# Audioaktor.net
KiCad netlist of a schematic drawn in EAGLE
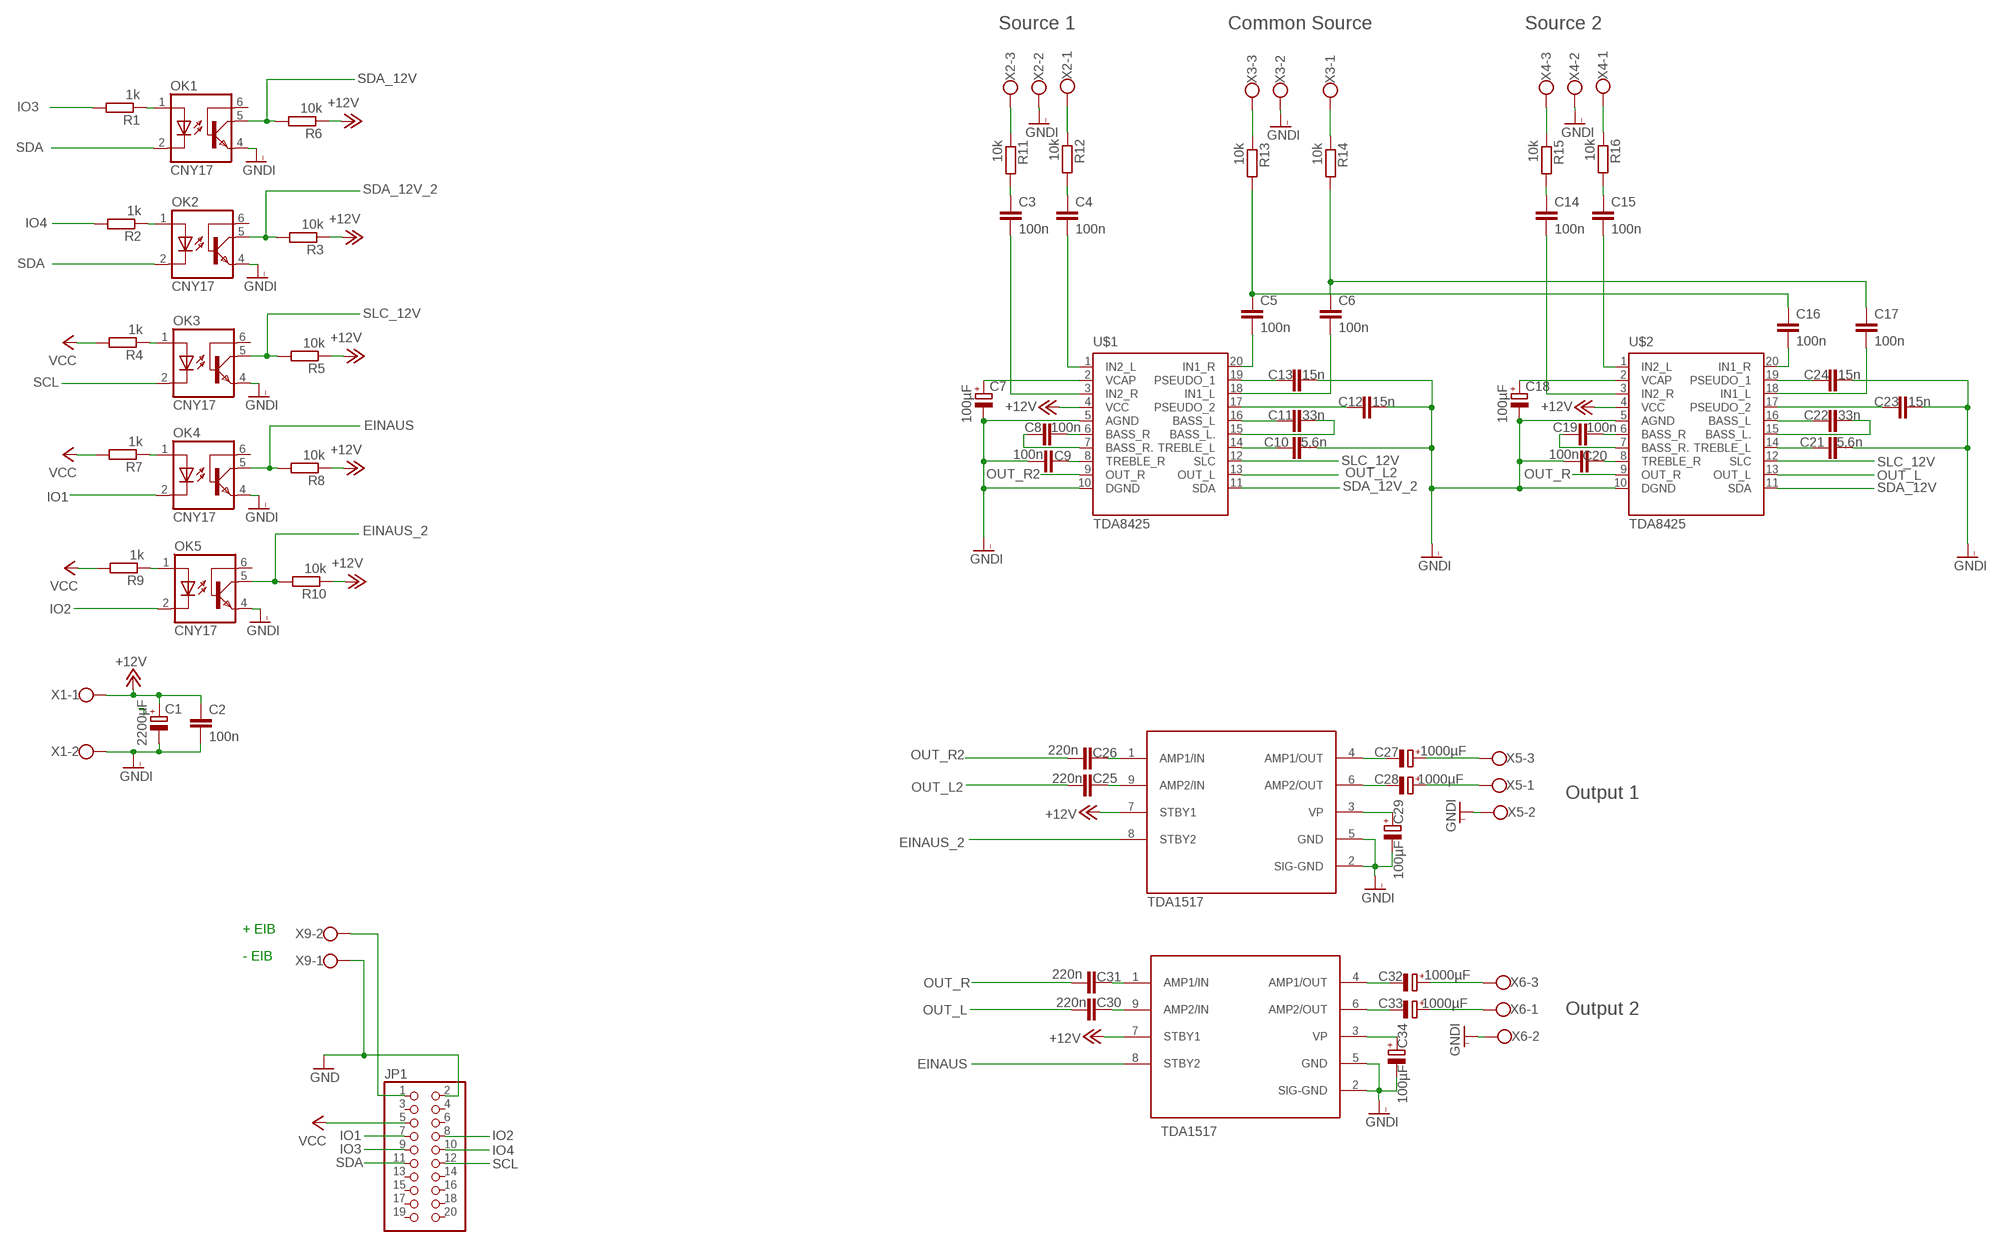
[diagram p0: schematic, sheet 1]

(export (version "E")
  (design (tool "Eeschema 10.0.6"))
  (components
    (comp (ref "C1")
      (value "2200µF")
      (footprint "eagle-import:E5-10,5")
      (libsource (lib "eagle-import") (part "CPOL-EUE5-10.5"))
    )
    (comp (ref "C2")
      (value "100n")
      (footprint "eagle-import:C050-030X075")
      (libsource (lib "eagle-import") (part "C-EU050-030X075"))
    )
    (comp (ref "C3")
      (value "100n")
      (footprint "eagle-import:C050-030X075")
      (libsource (lib "eagle-import") (part "C-EU050-030X075"))
    )
    (comp (ref "C4")
      (value "100n")
      (footprint "eagle-import:C050-030X075")
      (libsource (lib "eagle-import") (part "C-EU050-030X075"))
    )
    (comp (ref "C5")
      (value "100n")
      (footprint "eagle-import:C050-030X075")
      (libsource (lib "eagle-import") (part "C-EU050-030X075"))
    )
    (comp (ref "C6")
      (value "100n")
      (footprint "eagle-import:C050-030X075")
      (libsource (lib "eagle-import") (part "C-EU050-030X075"))
    )
    (comp (ref "C7")
      (value "100µF")
      (footprint "eagle-import:E5-10,5")
      (libsource (lib "eagle-import") (part "CPOL-EUE5-10.5"))
    )
    (comp (ref "C8")
      (value "100n")
      (footprint "eagle-import:C050-030X075")
      (libsource (lib "eagle-import") (part "C-EU050-030X075"))
    )
    (comp (ref "C9")
      (value "100n")
      (footprint "eagle-import:C050-030X075")
      (libsource (lib "eagle-import") (part "C-EU050-030X075"))
    )
    (comp (ref "C10")
      (value "5,6n")
      (footprint "eagle-import:C050-030X075")
      (libsource (lib "eagle-import") (part "C-EU050-030X075"))
    )
    (comp (ref "C11")
      (value "33n")
      (footprint "eagle-import:C050-030X075")
      (libsource (lib "eagle-import") (part "C-EU050-030X075"))
    )
    (comp (ref "C12")
      (value "15n")
      (footprint "eagle-import:C050-030X075")
      (libsource (lib "eagle-import") (part "C-EU050-030X075"))
    )
    (comp (ref "C13")
      (value "15n")
      (footprint "eagle-import:C050-030X075")
      (libsource (lib "eagle-import") (part "C-EU050-030X075"))
    )
    (comp (ref "C14")
      (value "100n")
      (footprint "eagle-import:C050-030X075")
      (libsource (lib "eagle-import") (part "C-EU050-030X075"))
    )
    (comp (ref "C15")
      (value "100n")
      (footprint "eagle-import:C050-030X075")
      (libsource (lib "eagle-import") (part "C-EU050-030X075"))
    )
    (comp (ref "C16")
      (value "100n")
      (footprint "eagle-import:C050-030X075")
      (libsource (lib "eagle-import") (part "C-EU050-030X075"))
    )
    (comp (ref "C17")
      (value "100n")
      (footprint "eagle-import:C050-030X075")
      (libsource (lib "eagle-import") (part "C-EU050-030X075"))
    )
    (comp (ref "C18")
      (value "100µF")
      (footprint "eagle-import:E5-10,5")
      (libsource (lib "eagle-import") (part "CPOL-EUE5-10.5"))
    )
    (comp (ref "C19")
      (value "100n")
      (footprint "eagle-import:C050-030X075")
      (libsource (lib "eagle-import") (part "C-EU050-030X075"))
    )
    (comp (ref "C20")
      (value "100n")
      (footprint "eagle-import:C050-030X075")
      (libsource (lib "eagle-import") (part "C-EU050-030X075"))
    )
    (comp (ref "C21")
      (value "5,6n")
      (footprint "eagle-import:C050-030X075")
      (libsource (lib "eagle-import") (part "C-EU050-030X075"))
    )
    (comp (ref "C22")
      (value "33n")
      (footprint "eagle-import:C050-030X075")
      (libsource (lib "eagle-import") (part "C-EU050-030X075"))
    )
    (comp (ref "C23")
      (value "15n")
      (footprint "eagle-import:C050-030X075")
      (libsource (lib "eagle-import") (part "C-EU050-030X075"))
    )
    (comp (ref "C24")
      (value "15n")
      (footprint "eagle-import:C050-030X075")
      (libsource (lib "eagle-import") (part "C-EU050-030X075"))
    )
    (comp (ref "C25")
      (value "220n")
      (footprint "eagle-import:C050-030X075")
      (libsource (lib "eagle-import") (part "C-EU050-030X075"))
    )
    (comp (ref "C26")
      (value "220n")
      (footprint "eagle-import:C050-030X075")
      (libsource (lib "eagle-import") (part "C-EU050-030X075"))
    )
    (comp (ref "C27")
      (value "1000µF")
      (footprint "eagle-import:E5-10,5")
      (libsource (lib "eagle-import") (part "CPOL-EUE5-10.5"))
    )
    (comp (ref "C28")
      (value "1000µF")
      (footprint "eagle-import:E5-10,5")
      (libsource (lib "eagle-import") (part "CPOL-EUE5-10.5"))
    )
    (comp (ref "C29")
      (value "100µF")
      (footprint "eagle-import:E5-10,5")
      (libsource (lib "eagle-import") (part "CPOL-EUE5-10.5"))
    )
    (comp (ref "C30")
      (value "220n")
      (footprint "eagle-import:C050-030X075")
      (libsource (lib "eagle-import") (part "C-EU050-030X075"))
    )
    (comp (ref "C31")
      (value "220n")
      (footprint "eagle-import:C050-030X075")
      (libsource (lib "eagle-import") (part "C-EU050-030X075"))
    )
    (comp (ref "C32")
      (value "1000µF")
      (footprint "eagle-import:E5-10,5")
      (libsource (lib "eagle-import") (part "CPOL-EUE5-10.5"))
    )
    (comp (ref "C33")
      (value "1000µF")
      (footprint "eagle-import:E5-10,5")
      (libsource (lib "eagle-import") (part "CPOL-EUE5-10.5"))
    )
    (comp (ref "C34")
      (value "100µF")
      (footprint "eagle-import:E5-10,5")
      (libsource (lib "eagle-import") (part "CPOL-EUE5-10.5"))
    )
    (comp (ref "JP1")
      (value "PINHD-2X10")
      (footprint "eagle-import:2X10")
      (libsource (lib "eagle-import") (part "PINHD-2X10"))
    )
    (comp (ref "OK1")
      (value "CNY17")
      (footprint "eagle-import:DIL06")
      (libsource (lib "eagle-import") (part "CNY17"))
    )
    (comp (ref "OK2")
      (value "CNY17")
      (footprint "eagle-import:DIL06")
      (libsource (lib "eagle-import") (part "CNY17"))
    )
    (comp (ref "OK3")
      (value "CNY17")
      (footprint "eagle-import:DIL06")
      (libsource (lib "eagle-import") (part "CNY17"))
    )
    (comp (ref "OK4")
      (value "CNY17")
      (footprint "eagle-import:DIL06")
      (libsource (lib "eagle-import") (part "CNY17"))
    )
    (comp (ref "OK5")
      (value "CNY17")
      (footprint "eagle-import:DIL06")
      (libsource (lib "eagle-import") (part "CNY17"))
    )
    (comp (ref "R1")
      (value "1k")
      (footprint "eagle-import:0204_7")
      (libsource (lib "eagle-import") (part "R-EU_0204/7"))
    )
    (comp (ref "R2")
      (value "1k")
      (footprint "eagle-import:0204_7")
      (libsource (lib "eagle-import") (part "R-EU_0204/7"))
    )
    (comp (ref "R3")
      (value "10k")
      (footprint "eagle-import:0204_7")
      (libsource (lib "eagle-import") (part "R-EU_0204/7"))
    )
    (comp (ref "R4")
      (value "1k")
      (footprint "eagle-import:0204_7")
      (libsource (lib "eagle-import") (part "R-EU_0204/7"))
    )
    (comp (ref "R5")
      (value "10k")
      (footprint "eagle-import:0204_7")
      (libsource (lib "eagle-import") (part "R-EU_0204/7"))
    )
    (comp (ref "R6")
      (value "10k")
      (footprint "eagle-import:0204_7")
      (libsource (lib "eagle-import") (part "R-EU_0204/7"))
    )
    (comp (ref "R7")
      (value "1k")
      (footprint "eagle-import:0204_7")
      (libsource (lib "eagle-import") (part "R-EU_0204/7"))
    )
    (comp (ref "R8")
      (value "10k")
      (footprint "eagle-import:0204_7")
      (libsource (lib "eagle-import") (part "R-EU_0204/7"))
    )
    (comp (ref "R9")
      (value "1k")
      (footprint "eagle-import:0204_7")
      (libsource (lib "eagle-import") (part "R-EU_0204/7"))
    )
    (comp (ref "R10")
      (value "10k")
      (footprint "eagle-import:0204_7")
      (libsource (lib "eagle-import") (part "R-EU_0204/7"))
    )
    (comp (ref "R11")
      (value "10k")
      (footprint "eagle-import:0204_7")
      (libsource (lib "eagle-import") (part "R-EU_0204/7"))
    )
    (comp (ref "R12")
      (value "10k")
      (footprint "eagle-import:0204_7")
      (libsource (lib "eagle-import") (part "R-EU_0204/7"))
    )
    (comp (ref "R13")
      (value "10k")
      (footprint "eagle-import:0204_7")
      (libsource (lib "eagle-import") (part "R-EU_0204/7"))
    )
    (comp (ref "R14")
      (value "10k")
      (footprint "eagle-import:0204_7")
      (libsource (lib "eagle-import") (part "R-EU_0204/7"))
    )
    (comp (ref "R15")
      (value "10k")
      (footprint "eagle-import:0204_7")
      (libsource (lib "eagle-import") (part "R-EU_0204/7"))
    )
    (comp (ref "R16")
      (value "10k")
      (footprint "eagle-import:0204_7")
      (libsource (lib "eagle-import") (part "R-EU_0204/7"))
    )
    (comp (ref "TDA1517")
      (value "TDA1517")
      (footprint "eagle-import:TDA1517")
      (libsource (lib "eagle-import") (part "TDA1517"))
    )
    (comp (ref "U$1")
      (value "TDA8425")
      (footprint "eagle-import:DIL20")
      (libsource (lib "eagle-import") (part "TDA8425"))
    )
    (comp (ref "U$2")
      (value "TDA8425")
      (footprint "eagle-import:DIL20")
      (libsource (lib "eagle-import") (part "TDA8425"))
    )
    (comp (ref "U$3")
      (value "TDA1517")
      (footprint "eagle-import:TDA1517")
      (libsource (lib "eagle-import") (part "TDA1517"))
    )
    (comp (ref "X1")
      (value "W237-102")
      (footprint "eagle-import:W237-102")
      (libsource (lib "eagle-import") (part "W237-102"))
    )
    (comp (ref "X2")
      (value "W237-103")
      (footprint "eagle-import:W237-103")
      (libsource (lib "eagle-import") (part "W237-103"))
    )
    (comp (ref "X3")
      (value "W237-103")
      (footprint "eagle-import:W237-103")
      (libsource (lib "eagle-import") (part "W237-103"))
    )
    (comp (ref "X4")
      (value "W237-103")
      (footprint "eagle-import:W237-103")
      (libsource (lib "eagle-import") (part "W237-103"))
    )
    (comp (ref "X5")
      (value "W237-103")
      (footprint "eagle-import:W237-103")
      (libsource (lib "eagle-import") (part "W237-103"))
    )
    (comp (ref "X6")
      (value "W237-103")
      (footprint "eagle-import:W237-103")
      (libsource (lib "eagle-import") (part "W237-103"))
    )
    (comp (ref "X9")
      (value "W237-102")
      (footprint "eagle-import:W237-102")
      (libsource (lib "eagle-import") (part "W237-102"))
    )
  )
  (nets
    (net (code "1") (name "+12V") (class "Default")
      (node (ref "C1") (pin "+") (pinfunction "+_+") (pintype "passive"))
      (node (ref "C2") (pin "1") (pinfunction "1_1") (pintype "passive"))
      (node (ref "R10") (pin "1") (pinfunction "1_1") (pintype "passive"))
      (node (ref "R3") (pin "1") (pinfunction "1_1") (pintype "passive"))
      (node (ref "R5") (pin "1") (pinfunction "1_1") (pintype "passive"))
      (node (ref "R6") (pin "1") (pinfunction "1_1") (pintype "passive"))
      (node (ref "R8") (pin "1") (pinfunction "1_1") (pintype "passive"))
      (node (ref "TDA1517") (pin "7") (pinfunction "STBY1_7") (pintype "bidirectional"))
      (node (ref "U$1") (pin "4") (pinfunction "VCC_4") (pintype "input"))
      (node (ref "U$2") (pin "4") (pinfunction "VCC_4") (pintype "input"))
      (node (ref "U$3") (pin "7") (pinfunction "STBY1_7") (pintype "bidirectional"))
      (node (ref "X1") (pin "1") (pinfunction "KL_1") (pintype "passive"))
    )
    (net (code "2") (name "/EINAUS") (class "Default")
      (node (ref "OK4") (pin "5") (pinfunction "COL_5") (pintype "passive"))
      (node (ref "R8") (pin "2") (pinfunction "2_2") (pintype "passive"))
      (node (ref "TDA1517") (pin "8") (pinfunction "STBY2_8") (pintype "bidirectional"))
    )
    (net (code "3") (name "/EINAUS_2") (class "Default")
      (node (ref "OK5") (pin "5") (pinfunction "COL_5") (pintype "passive"))
      (node (ref "R10") (pin "2") (pinfunction "2_2") (pintype "passive"))
      (node (ref "U$3") (pin "8") (pinfunction "STBY2_8") (pintype "bidirectional"))
    )
    (net (code "4") (name "/IO1") (class "Default")
      (node (ref "JP1") (pin "7") (pinfunction "7_7") (pintype "passive"))
      (node (ref "OK4") (pin "2") (pinfunction "C_2") (pintype "passive"))
    )
    (net (code "5") (name "/IO2") (class "Default")
      (node (ref "JP1") (pin "8") (pinfunction "8_8") (pintype "passive"))
      (node (ref "OK5") (pin "2") (pinfunction "C_2") (pintype "passive"))
    )
    (net (code "6") (name "/IO3") (class "Default")
      (node (ref "JP1") (pin "9") (pinfunction "9_9") (pintype "passive"))
      (node (ref "R1") (pin "2") (pinfunction "2_2") (pintype "passive"))
    )
    (net (code "7") (name "/IO4") (class "Default")
      (node (ref "JP1") (pin "10") (pinfunction "10_10") (pintype "passive"))
      (node (ref "R2") (pin "2") (pinfunction "2_2") (pintype "passive"))
    )
    (net (code "8") (name "/OUT_L") (class "Default")
      (node (ref "C30") (pin "1") (pinfunction "1_1") (pintype "passive"))
      (node (ref "U$2") (pin "13") (pinfunction "OUT_L_13") (pintype "input"))
    )
    (net (code "9") (name "/OUT_L2") (class "Default")
      (node (ref "C25") (pin "1") (pinfunction "1_1") (pintype "passive"))
      (node (ref "U$1") (pin "13") (pinfunction "OUT_L_13") (pintype "input"))
    )
    (net (code "10") (name "/OUT_R") (class "Default")
      (node (ref "C31") (pin "1") (pinfunction "1_1") (pintype "passive"))
      (node (ref "U$2") (pin "9") (pinfunction "OUT_R_9") (pintype "input"))
    )
    (net (code "11") (name "/OUT_R2") (class "Default")
      (node (ref "C26") (pin "1") (pinfunction "1_1") (pintype "passive"))
      (node (ref "U$1") (pin "9") (pinfunction "OUT_R_9") (pintype "input"))
    )
    (net (code "12") (name "/SCL") (class "Default")
      (node (ref "JP1") (pin "12") (pinfunction "12_12") (pintype "passive"))
      (node (ref "OK3") (pin "2") (pinfunction "C_2") (pintype "passive"))
    )
    (net (code "13") (name "/SDA") (class "Default")
      (node (ref "JP1") (pin "11") (pinfunction "11_11") (pintype "passive"))
      (node (ref "OK1") (pin "2") (pinfunction "C_2") (pintype "passive"))
      (node (ref "OK2") (pin "2") (pinfunction "C_2") (pintype "passive"))
    )
    (net (code "14") (name "/SDA_12V") (class "Default")
      (node (ref "OK1") (pin "5") (pinfunction "COL_5") (pintype "passive"))
      (node (ref "R6") (pin "2") (pinfunction "2_2") (pintype "passive"))
      (node (ref "U$2") (pin "11") (pinfunction "SDA_11") (pintype "input"))
    )
    (net (code "15") (name "/SDA_12V_2") (class "Default")
      (node (ref "OK2") (pin "5") (pinfunction "COL_5") (pintype "passive"))
      (node (ref "R3") (pin "2") (pinfunction "2_2") (pintype "passive"))
      (node (ref "U$1") (pin "11") (pinfunction "SDA_11") (pintype "input"))
    )
    (net (code "16") (name "/SLC_12V") (class "Default")
      (node (ref "OK3") (pin "5") (pinfunction "COL_5") (pintype "passive"))
      (node (ref "R5") (pin "2") (pinfunction "2_2") (pintype "passive"))
      (node (ref "U$1") (pin "12") (pinfunction "SLC_12") (pintype "passive"))
      (node (ref "U$2") (pin "12") (pinfunction "SLC_12") (pintype "passive"))
    )
    (net (code "17") (name "GND") (class "Default")
      (node (ref "JP1") (pin "2") (pinfunction "2_2") (pintype "passive"))
      (node (ref "X9") (pin "1") (pinfunction "KL_1") (pintype "passive"))
    )
    (net (code "18") (name "GNDI") (class "Default")
      (node (ref "C1") (pin "-") (pinfunction "-_-") (pintype "passive"))
      (node (ref "C10") (pin "2") (pinfunction "2_2") (pintype "passive"))
      (node (ref "C12") (pin "2") (pinfunction "2_2") (pintype "passive"))
      (node (ref "C13") (pin "2") (pinfunction "2_2") (pintype "passive"))
      (node (ref "C18") (pin "-") (pinfunction "-_-") (pintype "passive"))
      (node (ref "C2") (pin "2") (pinfunction "2_2") (pintype "passive"))
      (node (ref "C20") (pin "1") (pinfunction "1_1") (pintype "passive"))
      (node (ref "C21") (pin "2") (pinfunction "2_2") (pintype "passive"))
      (node (ref "C23") (pin "2") (pinfunction "2_2") (pintype "passive"))
      (node (ref "C24") (pin "2") (pinfunction "2_2") (pintype "passive"))
      (node (ref "C29") (pin "-") (pinfunction "-_-") (pintype "passive"))
      (node (ref "C34") (pin "-") (pinfunction "-_-") (pintype "passive"))
      (node (ref "C7") (pin "-") (pinfunction "-_-") (pintype "passive"))
      (node (ref "C9") (pin "1") (pinfunction "1_1") (pintype "passive"))
      (node (ref "OK1") (pin "4") (pinfunction "EMI_4") (pintype "passive"))
      (node (ref "OK2") (pin "4") (pinfunction "EMI_4") (pintype "passive"))
      (node (ref "OK3") (pin "4") (pinfunction "EMI_4") (pintype "passive"))
      (node (ref "OK4") (pin "4") (pinfunction "EMI_4") (pintype "passive"))
      (node (ref "OK5") (pin "4") (pinfunction "EMI_4") (pintype "passive"))
      (node (ref "TDA1517") (pin "2") (pinfunction "SIG-GND_2") (pintype "bidirectional"))
      (node (ref "TDA1517") (pin "5") (pinfunction "GND_5") (pintype "bidirectional"))
      (node (ref "U$1") (pin "10") (pinfunction "DGND_10") (pintype "input"))
      (node (ref "U$1") (pin "5") (pinfunction "AGND_5") (pintype "input"))
      (node (ref "U$2") (pin "10") (pinfunction "DGND_10") (pintype "input"))
      (node (ref "U$2") (pin "5") (pinfunction "AGND_5") (pintype "input"))
      (node (ref "U$3") (pin "2") (pinfunction "SIG-GND_2") (pintype "bidirectional"))
      (node (ref "U$3") (pin "5") (pinfunction "GND_5") (pintype "bidirectional"))
      (node (ref "X1") (pin "2") (pinfunction "KL_2") (pintype "passive"))
      (node (ref "X2") (pin "2") (pinfunction "KL_2") (pintype "passive"))
      (node (ref "X3") (pin "2") (pinfunction "KL_2") (pintype "passive"))
      (node (ref "X4") (pin "2") (pinfunction "KL_2") (pintype "passive"))
      (node (ref "X5") (pin "2") (pinfunction "KL_2") (pintype "passive"))
      (node (ref "X6") (pin "2") (pinfunction "KL_2") (pintype "passive"))
    )
    (net (code "19") (name "Net-(C3-Pad1)") (class "Default")
      (node (ref "C3") (pin "1") (pinfunction "1_1") (pintype "passive"))
      (node (ref "R11") (pin "2") (pinfunction "2_2") (pintype "passive"))
    )
    (net (code "20") (name "Net-(C4-Pad1)") (class "Default")
      (node (ref "C4") (pin "1") (pinfunction "1_1") (pintype "passive"))
      (node (ref "R12") (pin "2") (pinfunction "2_2") (pintype "passive"))
    )
    (net (code "21") (name "Net-(C14-Pad1)") (class "Default")
      (node (ref "C14") (pin "1") (pinfunction "1_1") (pintype "passive"))
      (node (ref "R15") (pin "2") (pinfunction "2_2") (pintype "passive"))
    )
    (net (code "22") (name "Net-(C15-Pad1)") (class "Default")
      (node (ref "C15") (pin "1") (pinfunction "1_1") (pintype "passive"))
      (node (ref "R16") (pin "2") (pinfunction "2_2") (pintype "passive"))
    )
    (net (code "23") (name "Net-(C16-Pad1)") (class "Default")
      (node (ref "C16") (pin "1") (pinfunction "1_1") (pintype "passive"))
      (node (ref "C5") (pin "1") (pinfunction "1_1") (pintype "passive"))
      (node (ref "R13") (pin "2") (pinfunction "2_2") (pintype "passive"))
    )
    (net (code "24") (name "Net-(C17-Pad1)") (class "Default")
      (node (ref "C17") (pin "1") (pinfunction "1_1") (pintype "passive"))
      (node (ref "C6") (pin "1") (pinfunction "1_1") (pintype "passive"))
      (node (ref "R14") (pin "2") (pinfunction "2_2") (pintype "passive"))
    )
    (net (code "25") (name "Net-(OK1-A)") (class "Default")
      (node (ref "OK1") (pin "1") (pinfunction "A_1") (pintype "passive"))
      (node (ref "R1") (pin "1") (pinfunction "1_1") (pintype "passive"))
    )
    (net (code "26") (name "Net-(OK2-A)") (class "Default")
      (node (ref "OK2") (pin "1") (pinfunction "A_1") (pintype "passive"))
      (node (ref "R2") (pin "1") (pinfunction "1_1") (pintype "passive"))
    )
    (net (code "27") (name "Net-(OK3-A)") (class "Default")
      (node (ref "OK3") (pin "1") (pinfunction "A_1") (pintype "passive"))
      (node (ref "R4") (pin "1") (pinfunction "1_1") (pintype "passive"))
    )
    (net (code "28") (name "Net-(OK4-A)") (class "Default")
      (node (ref "OK4") (pin "1") (pinfunction "A_1") (pintype "passive"))
      (node (ref "R7") (pin "1") (pinfunction "1_1") (pintype "passive"))
    )
    (net (code "29") (name "Net-(OK5-A)") (class "Default")
      (node (ref "OK5") (pin "1") (pinfunction "A_1") (pintype "passive"))
      (node (ref "R9") (pin "1") (pinfunction "1_1") (pintype "passive"))
    )
    (net (code "30") (name "Net-(TDA1517-AMP1{slash}IN)") (class "Default")
      (node (ref "C31") (pin "2") (pinfunction "2_2") (pintype "passive"))
      (node (ref "TDA1517") (pin "1") (pinfunction "AMP1/IN_1") (pintype "bidirectional"))
    )
    (net (code "31") (name "Net-(TDA1517-AMP1{slash}OUT)") (class "Default")
      (node (ref "C32") (pin "-") (pinfunction "-_-") (pintype "passive"))
      (node (ref "TDA1517") (pin "4") (pinfunction "AMP1/OUT_4") (pintype "bidirectional"))
    )
    (net (code "32") (name "Net-(TDA1517-AMP2{slash}IN)") (class "Default")
      (node (ref "C30") (pin "2") (pinfunction "2_2") (pintype "passive"))
      (node (ref "TDA1517") (pin "9") (pinfunction "AMP2/IN_9") (pintype "bidirectional"))
    )
    (net (code "33") (name "Net-(TDA1517-AMP2{slash}OUT)") (class "Default")
      (node (ref "C33") (pin "-") (pinfunction "-_-") (pintype "passive"))
      (node (ref "TDA1517") (pin "6") (pinfunction "AMP2/OUT_6") (pintype "bidirectional"))
    )
    (net (code "34") (name "Net-(TDA1517-VP)") (class "Default")
      (node (ref "C34") (pin "+") (pinfunction "+_+") (pintype "passive"))
      (node (ref "TDA1517") (pin "3") (pinfunction "VP_3") (pintype "bidirectional"))
    )
    (net (code "35") (name "Net-(U$1-BASS_L)") (class "Default")
      (node (ref "C11") (pin "1") (pinfunction "1_1") (pintype "passive"))
      (node (ref "U$1") (pin "16") (pinfunction "BASS_L_16") (pintype "output"))
    )
    (net (code "36") (name "Net-(U$1-BASS_L.)") (class "Default")
      (node (ref "C11") (pin "2") (pinfunction "2_2") (pintype "passive"))
      (node (ref "U$1") (pin "15") (pinfunction "BASS_L._15") (pintype "output"))
    )
    (net (code "37") (name "Net-(U$1-BASS_R)") (class "Default")
      (node (ref "C8") (pin "2") (pinfunction "2_2") (pintype "passive"))
      (node (ref "U$1") (pin "6") (pinfunction "BASS_R_6") (pintype "input"))
    )
    (net (code "38") (name "Net-(U$1-BASS_R.)") (class "Default")
      (node (ref "C8") (pin "1") (pinfunction "1_1") (pintype "passive"))
      (node (ref "U$1") (pin "7") (pinfunction "BASS_R._7") (pintype "input"))
    )
    (net (code "39") (name "Net-(U$1-IN1_L)") (class "Default")
      (node (ref "C6") (pin "2") (pinfunction "2_2") (pintype "passive"))
      (node (ref "U$1") (pin "18") (pinfunction "IN1_L_18") (pintype "output"))
    )
    (net (code "40") (name "Net-(U$1-IN1_R)") (class "Default")
      (node (ref "C5") (pin "2") (pinfunction "2_2") (pintype "passive"))
      (node (ref "U$1") (pin "20") (pinfunction "IN1_R_20") (pintype "passive"))
    )
    (net (code "41") (name "Net-(U$1-IN2_L)") (class "Default")
      (node (ref "C4") (pin "2") (pinfunction "2_2") (pintype "passive"))
      (node (ref "U$1") (pin "1") (pinfunction "IN2_L_1") (pintype "passive"))
    )
    (net (code "42") (name "Net-(U$1-IN2_R)") (class "Default")
      (node (ref "C3") (pin "2") (pinfunction "2_2") (pintype "passive"))
      (node (ref "U$1") (pin "3") (pinfunction "IN2_R_3") (pintype "passive"))
    )
    (net (code "43") (name "Net-(U$1-PSEUDO_1)") (class "Default")
      (node (ref "C13") (pin "1") (pinfunction "1_1") (pintype "passive"))
      (node (ref "U$1") (pin "19") (pinfunction "PSEUDO_1_19") (pintype "passive"))
    )
    (net (code "44") (name "Net-(U$1-PSEUDO_2)") (class "Default")
      (node (ref "C12") (pin "1") (pinfunction "1_1") (pintype "passive"))
      (node (ref "U$1") (pin "17") (pinfunction "PSEUDO_2_17") (pintype "passive"))
    )
    (net (code "45") (name "Net-(U$1-TREBLE_L)") (class "Default")
      (node (ref "C10") (pin "1") (pinfunction "1_1") (pintype "passive"))
      (node (ref "U$1") (pin "14") (pinfunction "TREBLE_L_14") (pintype "output"))
    )
    (net (code "46") (name "Net-(U$1-TREBLE_R)") (class "Default")
      (node (ref "C9") (pin "2") (pinfunction "2_2") (pintype "passive"))
      (node (ref "U$1") (pin "8") (pinfunction "TREBLE_R_8") (pintype "input"))
    )
    (net (code "47") (name "Net-(U$1-VCAP)") (class "Default")
      (node (ref "C7") (pin "+") (pinfunction "+_+") (pintype "passive"))
      (node (ref "U$1") (pin "2") (pinfunction "VCAP_2") (pintype "passive"))
    )
    (net (code "48") (name "Net-(U$2-BASS_L)") (class "Default")
      (node (ref "C22") (pin "1") (pinfunction "1_1") (pintype "passive"))
      (node (ref "U$2") (pin "16") (pinfunction "BASS_L_16") (pintype "output"))
    )
    (net (code "49") (name "Net-(U$2-BASS_L.)") (class "Default")
      (node (ref "C22") (pin "2") (pinfunction "2_2") (pintype "passive"))
      (node (ref "U$2") (pin "15") (pinfunction "BASS_L._15") (pintype "output"))
    )
    (net (code "50") (name "Net-(U$2-BASS_R)") (class "Default")
      (node (ref "C19") (pin "2") (pinfunction "2_2") (pintype "passive"))
      (node (ref "U$2") (pin "6") (pinfunction "BASS_R_6") (pintype "input"))
    )
    (net (code "51") (name "Net-(U$2-BASS_R.)") (class "Default")
      (node (ref "C19") (pin "1") (pinfunction "1_1") (pintype "passive"))
      (node (ref "U$2") (pin "7") (pinfunction "BASS_R._7") (pintype "input"))
    )
    (net (code "52") (name "Net-(U$2-IN1_L)") (class "Default")
      (node (ref "C17") (pin "2") (pinfunction "2_2") (pintype "passive"))
      (node (ref "U$2") (pin "18") (pinfunction "IN1_L_18") (pintype "output"))
    )
    (net (code "53") (name "Net-(U$2-IN1_R)") (class "Default")
      (node (ref "C16") (pin "2") (pinfunction "2_2") (pintype "passive"))
      (node (ref "U$2") (pin "20") (pinfunction "IN1_R_20") (pintype "passive"))
    )
    (net (code "54") (name "Net-(U$2-IN2_L)") (class "Default")
      (node (ref "C15") (pin "2") (pinfunction "2_2") (pintype "passive"))
      (node (ref "U$2") (pin "1") (pinfunction "IN2_L_1") (pintype "passive"))
    )
    (net (code "55") (name "Net-(U$2-IN2_R)") (class "Default")
      (node (ref "C14") (pin "2") (pinfunction "2_2") (pintype "passive"))
      (node (ref "U$2") (pin "3") (pinfunction "IN2_R_3") (pintype "passive"))
    )
    (net (code "56") (name "Net-(U$2-PSEUDO_1)") (class "Default")
      (node (ref "C24") (pin "1") (pinfunction "1_1") (pintype "passive"))
      (node (ref "U$2") (pin "19") (pinfunction "PSEUDO_1_19") (pintype "passive"))
    )
    (net (code "57") (name "Net-(U$2-PSEUDO_2)") (class "Default")
      (node (ref "C23") (pin "1") (pinfunction "1_1") (pintype "passive"))
      (node (ref "U$2") (pin "17") (pinfunction "PSEUDO_2_17") (pintype "passive"))
    )
    (net (code "58") (name "Net-(U$2-TREBLE_L)") (class "Default")
      (node (ref "C21") (pin "1") (pinfunction "1_1") (pintype "passive"))
      (node (ref "U$2") (pin "14") (pinfunction "TREBLE_L_14") (pintype "output"))
    )
    (net (code "59") (name "Net-(U$2-TREBLE_R)") (class "Default")
      (node (ref "C20") (pin "2") (pinfunction "2_2") (pintype "passive"))
      (node (ref "U$2") (pin "8") (pinfunction "TREBLE_R_8") (pintype "input"))
    )
    (net (code "60") (name "Net-(U$2-VCAP)") (class "Default")
      (node (ref "C18") (pin "+") (pinfunction "+_+") (pintype "passive"))
      (node (ref "U$2") (pin "2") (pinfunction "VCAP_2") (pintype "passive"))
    )
    (net (code "61") (name "Net-(U$3-AMP1{slash}IN)") (class "Default")
      (node (ref "C26") (pin "2") (pinfunction "2_2") (pintype "passive"))
      (node (ref "U$3") (pin "1") (pinfunction "AMP1/IN_1") (pintype "bidirectional"))
    )
    (net (code "62") (name "Net-(U$3-AMP1{slash}OUT)") (class "Default")
      (node (ref "C27") (pin "-") (pinfunction "-_-") (pintype "passive"))
      (node (ref "U$3") (pin "4") (pinfunction "AMP1/OUT_4") (pintype "bidirectional"))
    )
    (net (code "63") (name "Net-(U$3-AMP2{slash}IN)") (class "Default")
      (node (ref "C25") (pin "2") (pinfunction "2_2") (pintype "passive"))
      (node (ref "U$3") (pin "9") (pinfunction "AMP2/IN_9") (pintype "bidirectional"))
    )
    (net (code "64") (name "Net-(U$3-AMP2{slash}OUT)") (class "Default")
      (node (ref "C28") (pin "-") (pinfunction "-_-") (pintype "passive"))
      (node (ref "U$3") (pin "6") (pinfunction "AMP2/OUT_6") (pintype "bidirectional"))
    )
    (net (code "65") (name "Net-(U$3-VP)") (class "Default")
      (node (ref "C29") (pin "+") (pinfunction "+_+") (pintype "passive"))
      (node (ref "U$3") (pin "3") (pinfunction "VP_3") (pintype "bidirectional"))
    )
    (net (code "66") (name "Net-(X2A-KL)") (class "Default")
      (node (ref "R12") (pin "1") (pinfunction "1_1") (pintype "passive"))
      (node (ref "X2") (pin "1") (pinfunction "KL_1") (pintype "passive"))
    )
    (net (code "67") (name "Net-(X2C-KL)") (class "Default")
      (node (ref "R11") (pin "1") (pinfunction "1_1") (pintype "passive"))
      (node (ref "X2") (pin "3") (pinfunction "KL_3") (pintype "passive"))
    )
    (net (code "68") (name "Net-(X3A-KL)") (class "Default")
      (node (ref "R14") (pin "1") (pinfunction "1_1") (pintype "passive"))
      (node (ref "X3") (pin "1") (pinfunction "KL_1") (pintype "passive"))
    )
    (net (code "69") (name "Net-(X3C-KL)") (class "Default")
      (node (ref "R13") (pin "1") (pinfunction "1_1") (pintype "passive"))
      (node (ref "X3") (pin "3") (pinfunction "KL_3") (pintype "passive"))
    )
    (net (code "70") (name "Net-(X4A-KL)") (class "Default")
      (node (ref "R16") (pin "1") (pinfunction "1_1") (pintype "passive"))
      (node (ref "X4") (pin "1") (pinfunction "KL_1") (pintype "passive"))
    )
    (net (code "71") (name "Net-(X4C-KL)") (class "Default")
      (node (ref "R15") (pin "1") (pinfunction "1_1") (pintype "passive"))
      (node (ref "X4") (pin "3") (pinfunction "KL_3") (pintype "passive"))
    )
    (net (code "72") (name "Net-(X5A-KL)") (class "Default")
      (node (ref "C28") (pin "+") (pinfunction "+_+") (pintype "passive"))
      (node (ref "X5") (pin "1") (pinfunction "KL_1") (pintype "passive"))
    )
    (net (code "73") (name "Net-(X5C-KL)") (class "Default")
      (node (ref "C27") (pin "+") (pinfunction "+_+") (pintype "passive"))
      (node (ref "X5") (pin "3") (pinfunction "KL_3") (pintype "passive"))
    )
    (net (code "74") (name "Net-(X6A-KL)") (class "Default")
      (node (ref "C33") (pin "+") (pinfunction "+_+") (pintype "passive"))
      (node (ref "X6") (pin "1") (pinfunction "KL_1") (pintype "passive"))
    )
    (net (code "75") (name "Net-(X6C-KL)") (class "Default")
      (node (ref "C32") (pin "+") (pinfunction "+_+") (pintype "passive"))
      (node (ref "X6") (pin "3") (pinfunction "KL_3") (pintype "passive"))
    )
    (net (code "76") (name "Net-(X9B-KL)") (class "Default")
      (node (ref "JP1") (pin "1") (pinfunction "1_1") (pintype "passive"))
      (node (ref "X9") (pin "2") (pinfunction "KL_2") (pintype "passive"))
    )
    (net (code "77") (name "VCC") (class "Default")
      (node (ref "JP1") (pin "5") (pinfunction "5_5") (pintype "passive"))
      (node (ref "R4") (pin "2") (pinfunction "2_2") (pintype "passive"))
      (node (ref "R7") (pin "2") (pinfunction "2_2") (pintype "passive"))
      (node (ref "R9") (pin "2") (pinfunction "2_2") (pintype "passive"))
    )
    (net (code "78") (name "unconnected-(JP1-Pad3)") (class "Default")
      (node (ref "JP1") (pin "3") (pinfunction "3_3") (pintype "passive"))
    )
    (net (code "79") (name "unconnected-(JP1-Pad4)") (class "Default")
      (node (ref "JP1") (pin "4") (pinfunction "4_4") (pintype "passive"))
    )
    (net (code "80") (name "unconnected-(JP1-Pad6)") (class "Default")
      (node (ref "JP1") (pin "6") (pinfunction "6_6") (pintype "passive"))
    )
    (net (code "81") (name "unconnected-(JP1-Pad13)") (class "Default")
      (node (ref "JP1") (pin "13") (pinfunction "13_13") (pintype "passive"))
    )
    (net (code "82") (name "unconnected-(JP1-Pad14)") (class "Default")
      (node (ref "JP1") (pin "14") (pinfunction "14_14") (pintype "passive"))
    )
    (net (code "83") (name "unconnected-(JP1-Pad15)") (class "Default")
      (node (ref "JP1") (pin "15") (pinfunction "15_15") (pintype "passive"))
    )
    (net (code "84") (name "unconnected-(JP1-Pad16)") (class "Default")
      (node (ref "JP1") (pin "16") (pinfunction "16_16") (pintype "passive"))
    )
    (net (code "85") (name "unconnected-(JP1-Pad17)") (class "Default")
      (node (ref "JP1") (pin "17") (pinfunction "17_17") (pintype "passive"))
    )
    (net (code "86") (name "unconnected-(JP1-Pad18)") (class "Default")
      (node (ref "JP1") (pin "18") (pinfunction "18_18") (pintype "passive"))
    )
    (net (code "87") (name "unconnected-(JP1-Pad19)") (class "Default")
      (node (ref "JP1") (pin "19") (pinfunction "19_19") (pintype "passive"))
    )
    (net (code "88") (name "unconnected-(JP1-Pad20)") (class "Default")
      (node (ref "JP1") (pin "20") (pinfunction "20_20") (pintype "passive"))
    )
    (net (code "89") (name "unconnected-(OK1-BAS-Pad6)") (class "Default")
      (node (ref "OK1") (pin "6") (pinfunction "BAS_6") (pintype "passive"))
    )
    (net (code "90") (name "unconnected-(OK2-BAS-Pad6)") (class "Default")
      (node (ref "OK2") (pin "6") (pinfunction "BAS_6") (pintype "passive"))
    )
    (net (code "91") (name "unconnected-(OK3-BAS-Pad6)") (class "Default")
      (node (ref "OK3") (pin "6") (pinfunction "BAS_6") (pintype "passive"))
    )
    (net (code "92") (name "unconnected-(OK4-BAS-Pad6)") (class "Default")
      (node (ref "OK4") (pin "6") (pinfunction "BAS_6") (pintype "passive"))
    )
    (net (code "93") (name "unconnected-(OK5-BAS-Pad6)") (class "Default")
      (node (ref "OK5") (pin "6") (pinfunction "BAS_6") (pintype "passive"))
    )
  )
)
